# stereo-encoder-nano.net
KiCad netlist of a schematic drawn in EAGLE
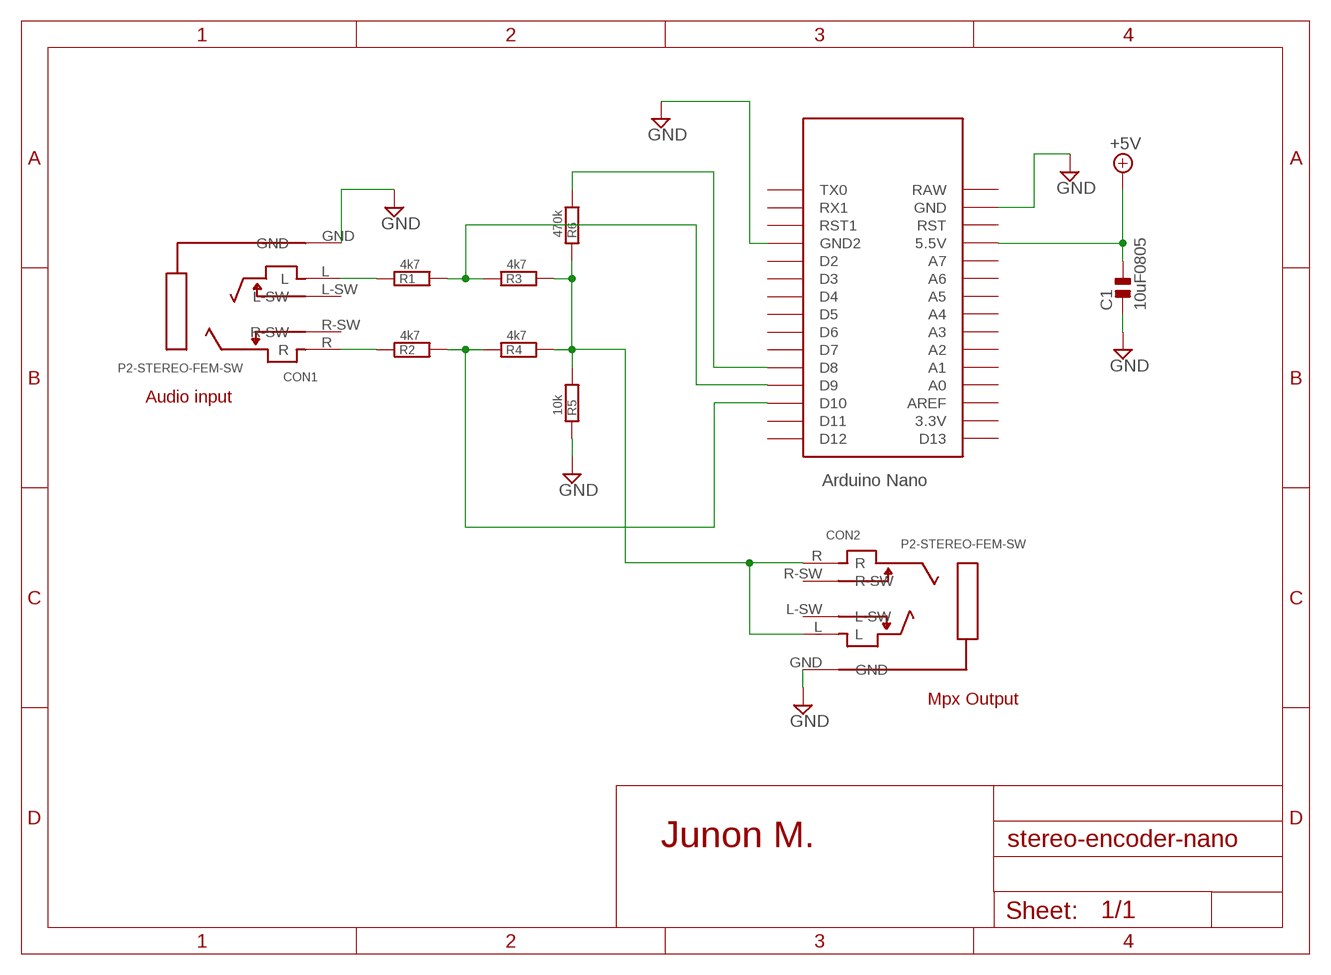
[diagram p0: schematic, sheet 1]

(export (version "E")
  (design (tool "Eeschema 10.0.6"))
  (components
    (comp (ref "C1")
      (value "10uF0805")
      (footprint "eagle-import:C0805")
      (libsource (lib "eagle-import") (part "C-SMD-0805"))
    )
    (comp (ref "CON1")
      (value "P2-STEREO-FEM-SW")
      (footprint "eagle-import:P2-STEREO-FEM-SW")
      (libsource (lib "eagle-import") (part "P2-STEREO-FEM-SW"))
    )
    (comp (ref "CON2")
      (value "P2-STEREO-FEM-SW")
      (footprint "eagle-import:P2-STEREO-FEM-SW")
      (libsource (lib "eagle-import") (part "P2-STEREO-FEM-SW"))
    )
    (comp (ref "R1")
      (value "4k7")
      (footprint "eagle-import:0207_10")
      (libsource (lib "eagle-import") (part "1/4W"))
    )
    (comp (ref "R2")
      (value "4k7")
      (footprint "eagle-import:0207_10")
      (libsource (lib "eagle-import") (part "1/4W"))
    )
    (comp (ref "R3")
      (value "4k7")
      (footprint "eagle-import:0207_10")
      (libsource (lib "eagle-import") (part "1/4W"))
    )
    (comp (ref "R4")
      (value "4k7")
      (footprint "eagle-import:0207_10")
      (libsource (lib "eagle-import") (part "1/4W"))
    )
    (comp (ref "R5")
      (value "10k")
      (footprint "eagle-import:0207_10")
      (libsource (lib "eagle-import") (part "1/4W"))
    )
    (comp (ref "R6")
      (value "470k")
      (footprint "eagle-import:0207_10")
      (libsource (lib "eagle-import") (part "1/4W"))
    )
    (comp (ref "U$1")
      (value "NANO")
      (footprint "eagle-import:NANO")
      (libsource (lib "eagle-import") (part "NANO"))
    )
  )
  (nets
    (net (code "1") (name "+5V") (class "Default")
      (node (ref "C1") (pin "2") (pinfunction "2_2") (pintype "passive"))
      (node (ref "U$1") (pin "5V") (pinfunction "5.5V_5V") (pintype "bidirectional"))
    )
    (net (code "2") (name "GND") (class "Default")
      (node (ref "C1") (pin "1") (pinfunction "1_1") (pintype "passive"))
      (node (ref "CON1") (pin "GND") (pinfunction "GND_GND") (pintype "passive"))
      (node (ref "CON2") (pin "GND") (pinfunction "GND_GND") (pintype "passive"))
      (node (ref "R5") (pin "1") (pinfunction "1_1") (pintype "passive"))
      (node (ref "U$1") (pin "GND") (pinfunction "GND_GND") (pintype "bidirectional"))
      (node (ref "U$1") (pin "GND1") (pinfunction "GND2_GND1") (pintype "bidirectional"))
    )
    (net (code "3") (name "Net-(CON1-PadL)") (class "Default")
      (node (ref "CON1") (pin "L") (pinfunction "L_L") (pintype "passive"))
      (node (ref "R1") (pin "1") (pinfunction "1_1") (pintype "passive"))
    )
    (net (code "4") (name "Net-(CON1-PadR)") (class "Default")
      (node (ref "CON1") (pin "R") (pinfunction "R_R") (pintype "passive"))
      (node (ref "R2") (pin "1") (pinfunction "1_1") (pintype "passive"))
    )
    (net (code "5") (name "Net-(CON2-PadL)") (class "Default")
      (node (ref "CON2") (pin "L") (pinfunction "L_L") (pintype "passive"))
      (node (ref "CON2") (pin "R") (pinfunction "R_R") (pintype "passive"))
      (node (ref "R3") (pin "2") (pinfunction "2_2") (pintype "passive"))
      (node (ref "R4") (pin "2") (pinfunction "2_2") (pintype "passive"))
      (node (ref "R5") (pin "2") (pinfunction "2_2") (pintype "passive"))
      (node (ref "R6") (pin "1") (pinfunction "1_1") (pintype "passive"))
    )
    (net (code "6") (name "Net-(R1-Pad2)") (class "Default")
      (node (ref "R1") (pin "2") (pinfunction "2_2") (pintype "passive"))
      (node (ref "R3") (pin "1") (pinfunction "1_1") (pintype "passive"))
      (node (ref "U$1") (pin "D9") (pinfunction "D9_D9") (pintype "bidirectional"))
    )
    (net (code "7") (name "Net-(R2-Pad2)") (class "Default")
      (node (ref "R2") (pin "2") (pinfunction "2_2") (pintype "passive"))
      (node (ref "R4") (pin "1") (pinfunction "1_1") (pintype "passive"))
      (node (ref "U$1") (pin "D10") (pinfunction "D10_D10") (pintype "bidirectional"))
    )
    (net (code "8") (name "Net-(R6-Pad2)") (class "Default")
      (node (ref "R6") (pin "2") (pinfunction "2_2") (pintype "passive"))
      (node (ref "U$1") (pin "D8") (pinfunction "D8_D8") (pintype "bidirectional"))
    )
    (net (code "9") (name "unconnected-(CON1-PadL-SW)") (class "Default")
      (node (ref "CON1") (pin "L-SW") (pinfunction "L-SW_L-SW") (pintype "passive"))
    )
    (net (code "10") (name "unconnected-(CON1-PadR-SW)") (class "Default")
      (node (ref "CON1") (pin "R-SW") (pinfunction "R-SW_R-SW") (pintype "passive"))
    )
    (net (code "11") (name "unconnected-(CON2-PadL-SW)") (class "Default")
      (node (ref "CON2") (pin "L-SW") (pinfunction "L-SW_L-SW") (pintype "passive"))
    )
    (net (code "12") (name "unconnected-(CON2-PadR-SW)") (class "Default")
      (node (ref "CON2") (pin "R-SW") (pinfunction "R-SW_R-SW") (pintype "passive"))
    )
    (net (code "13") (name "unconnected-(U$1-Pad3.3V)") (class "Default")
      (node (ref "U$1") (pin "3.3V") (pinfunction "3.3V_3.3V") (pintype "bidirectional"))
    )
    (net (code "14") (name "unconnected-(U$1-PadA0)") (class "Default")
      (node (ref "U$1") (pin "A0") (pinfunction "A0_A0") (pintype "bidirectional"))
    )
    (net (code "15") (name "unconnected-(U$1-PadA1)") (class "Default")
      (node (ref "U$1") (pin "A1") (pinfunction "A1_A1") (pintype "bidirectional"))
    )
    (net (code "16") (name "unconnected-(U$1-PadA2)") (class "Default")
      (node (ref "U$1") (pin "A2") (pinfunction "A2_A2") (pintype "bidirectional"))
    )
    (net (code "17") (name "unconnected-(U$1-PadA3)") (class "Default")
      (node (ref "U$1") (pin "A3") (pinfunction "A3_A3") (pintype "bidirectional"))
    )
    (net (code "18") (name "unconnected-(U$1-PadA4)") (class "Default")
      (node (ref "U$1") (pin "A4") (pinfunction "A4_A4") (pintype "bidirectional"))
    )
    (net (code "19") (name "unconnected-(U$1-PadA5)") (class "Default")
      (node (ref "U$1") (pin "A5") (pinfunction "A5_A5") (pintype "bidirectional"))
    )
    (net (code "20") (name "unconnected-(U$1-PadA6)") (class "Default")
      (node (ref "U$1") (pin "A6") (pinfunction "A6_A6") (pintype "bidirectional"))
    )
    (net (code "21") (name "unconnected-(U$1-PadA7)") (class "Default")
      (node (ref "U$1") (pin "A7") (pinfunction "A7_A7") (pintype "bidirectional"))
    )
    (net (code "22") (name "unconnected-(U$1-PadAREF)") (class "Default")
      (node (ref "U$1") (pin "AREF") (pinfunction "AREF_AREF") (pintype "bidirectional"))
    )
    (net (code "23") (name "unconnected-(U$1-PadD2)") (class "Default")
      (node (ref "U$1") (pin "D2") (pinfunction "D2_D2") (pintype "bidirectional"))
    )
    (net (code "24") (name "unconnected-(U$1-PadD3)") (class "Default")
      (node (ref "U$1") (pin "D3") (pinfunction "D3_D3") (pintype "bidirectional"))
    )
    (net (code "25") (name "unconnected-(U$1-PadD4)") (class "Default")
      (node (ref "U$1") (pin "D4") (pinfunction "D4_D4") (pintype "bidirectional"))
    )
    (net (code "26") (name "unconnected-(U$1-PadD5)") (class "Default")
      (node (ref "U$1") (pin "D5") (pinfunction "D5_D5") (pintype "bidirectional"))
    )
    (net (code "27") (name "unconnected-(U$1-PadD6)") (class "Default")
      (node (ref "U$1") (pin "D6") (pinfunction "D6_D6") (pintype "bidirectional"))
    )
    (net (code "28") (name "unconnected-(U$1-PadD7)") (class "Default")
      (node (ref "U$1") (pin "D7") (pinfunction "D7_D7") (pintype "bidirectional"))
    )
    (net (code "29") (name "unconnected-(U$1-PadD11)") (class "Default")
      (node (ref "U$1") (pin "D11") (pinfunction "D11_D11") (pintype "bidirectional"))
    )
    (net (code "30") (name "unconnected-(U$1-PadD12)") (class "Default")
      (node (ref "U$1") (pin "D12") (pinfunction "D12_D12") (pintype "bidirectional"))
    )
    (net (code "31") (name "unconnected-(U$1-PadD13)") (class "Default")
      (node (ref "U$1") (pin "D13") (pinfunction "D13_D13") (pintype "bidirectional"))
    )
    (net (code "32") (name "unconnected-(U$1-PadICSP1)") (class "Default")
      (node (ref "U$1") (pin "ICSP1") (pinfunction "ICSP1_ICSP1") (pintype "bidirectional"))
    )
    (net (code "33") (name "unconnected-(U$1-PadICSP2)") (class "Default")
      (node (ref "U$1") (pin "ICSP2") (pinfunction "ICSP2_ICSP2") (pintype "bidirectional"))
    )
    (net (code "34") (name "unconnected-(U$1-PadICSP3)") (class "Default")
      (node (ref "U$1") (pin "ICSP3") (pinfunction "ICSP3_ICSP3") (pintype "bidirectional"))
    )
    (net (code "35") (name "unconnected-(U$1-PadICSP4)") (class "Default")
      (node (ref "U$1") (pin "ICSP4") (pinfunction "ICSP4_ICSP4") (pintype "bidirectional"))
    )
    (net (code "36") (name "unconnected-(U$1-PadICSP5)") (class "Default")
      (node (ref "U$1") (pin "ICSP5") (pinfunction "ICSP5_ICSP5") (pintype "bidirectional"))
    )
    (net (code "37") (name "unconnected-(U$1-PadICSP6)") (class "Default")
      (node (ref "U$1") (pin "ICSP6") (pinfunction "ICSP6_ICSP6") (pintype "bidirectional"))
    )
    (net (code "38") (name "unconnected-(U$1-PadRAW)") (class "Default")
      (node (ref "U$1") (pin "RAW") (pinfunction "RAW_RAW") (pintype "bidirectional"))
    )
    (net (code "39") (name "unconnected-(U$1-PadRST)") (class "Default")
      (node (ref "U$1") (pin "RST") (pinfunction "RST_RST") (pintype "bidirectional"))
    )
    (net (code "40") (name "unconnected-(U$1-PadRST1)") (class "Default")
      (node (ref "U$1") (pin "RST1") (pinfunction "RST1_RST1") (pintype "bidirectional"))
    )
    (net (code "41") (name "unconnected-(U$1-PadRX1)") (class "Default")
      (node (ref "U$1") (pin "RX1") (pinfunction "RX1_RX1") (pintype "bidirectional"))
    )
    (net (code "42") (name "unconnected-(U$1-PadTX0)") (class "Default")
      (node (ref "U$1") (pin "TX0") (pinfunction "TX0_TX0") (pintype "bidirectional"))
    )
  )
)
